# HDMI.net
KiCad netlist of a schematic drawn in Altium Designer
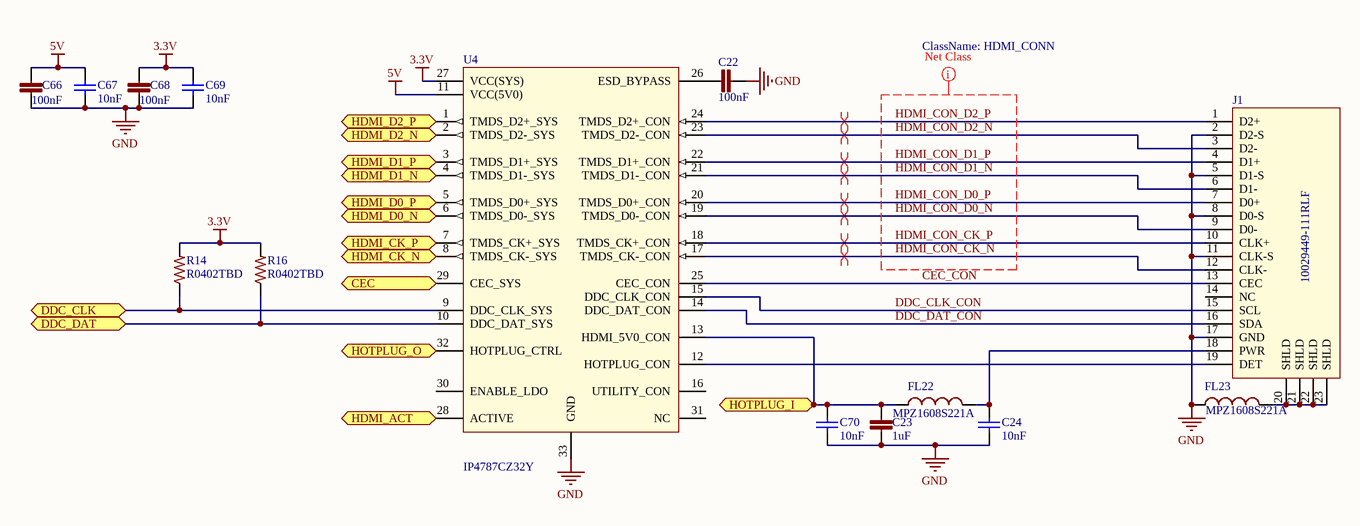
[diagram p0: HDMI.SchDoc]

(export (version "E")
  (design (tool "Eeschema 10.0.6"))
  (components
    (comp (ref "C22")
      (value "100nF")
      (footprint "C0402")
      (description "CAP CER 0402 100nF 16V 10% X7R")
      (fields
        (field (name "MANUFACTURERPARTNUMBER") "GRM155R71C104KA88D")
        (field (name "PUBLISHER") "UltiMachine")
      )
      (libsource (lib "") (part "GRM155R71C104KA88D_1"))
    )
    (comp (ref "C23")
      (value "1uF")
      (footprint "C0402")
      (description "CAP CER 0402 1uF 6.3V 10% X5R")
      (fields
        (field (name "MANUFACTURERPARTNUMBER") "GRM155R60J105KE19D")
        (field (name "PUBLISHER") "UltiMachine")
      )
      (libsource (lib "3Delight") (part "GRM155R60J105KE19D"))
    )
    (comp (ref "C24")
      (value "10nF")
      (footprint "C0402")
      (description "CAP CER 10nF 50V X7R 0402")
      (fields
        (field (name "MFR PART #") "GRM155R71H103JA88D")
        (field (name "MFR") "Murata")
        (field (name "PUBLISHER") "Ultimachine")
      )
      (libsource (lib "Tigershark3D") (part "GRM155R71H103JA88D"))
    )
    (comp (ref "C66")
      (value "100nF")
      (footprint "C0402")
      (description "CAP CER 0402 100nF 16V 10% X7R")
      (fields
        (field (name "MANUFACTURERPARTNUMBER") "GRM155R71C104KA88D")
        (field (name "PUBLISHER") "UltiMachine")
      )
      (libsource (lib "3Delight") (part "GRM155R71C104KA88D"))
    )
    (comp (ref "C67")
      (value "10nF")
      (footprint "C0402")
      (description "CAP CER 10nF 50V X7R 0402")
      (fields
        (field (name "MFR PART #") "GRM155R71H103JA88D")
        (field (name "MFR") "Murata")
        (field (name "PUBLISHER") "Ultimachine")
      )
      (libsource (lib "Tigershark3D") (part "GRM155R71H103JA88D"))
    )
    (comp (ref "C68")
      (value "100nF")
      (footprint "C0402")
      (description "CAP CER 0402 100nF 16V 10% X7R")
      (fields
        (field (name "MANUFACTURERPARTNUMBER") "GRM155R71C104KA88D")
        (field (name "PUBLISHER") "UltiMachine")
      )
      (libsource (lib "3Delight") (part "GRM155R71C104KA88D"))
    )
    (comp (ref "C69")
      (value "10nF")
      (footprint "C0402")
      (description "CAP CER 10nF 50V X7R 0402")
      (fields
        (field (name "MFR PART #") "GRM155R71H103JA88D")
        (field (name "MFR") "Murata")
        (field (name "PUBLISHER") "Ultimachine")
      )
      (libsource (lib "Tigershark3D") (part "GRM155R71H103JA88D"))
    )
    (comp (ref "C70")
      (value "10nF")
      (footprint "C0402")
      (description "CAP CER 10nF 50V X7R 0402")
      (fields
        (field (name "MFR PART #") "GRM155R71H103JA88D")
        (field (name "MFR") "Murata")
        (field (name "PUBLISHER") "Ultimachine")
      )
      (libsource (lib "Tigershark3D") (part "GRM155R71H103JA88D"))
    )
    (comp (ref "FL22")
      (value "MPZ1608S221A")
      (footprint "C0603")
      (description "Ferrite")
      (fields (field (name "PUBLISHER") "UltiMachine"))
      (libsource (lib "3Delight") (part "MPZ1608S221A"))
    )
    (comp (ref "FL23")
      (value "MPZ1608S221A")
      (footprint "C0603")
      (description "Ferrite")
      (fields (field (name "PUBLISHER") "UltiMachine"))
      (libsource (lib "3Delight") (part "MPZ1608S221A"))
    )
    (comp (ref "J1")
      (value "10029449-111RLF")
      (footprint "10029449-111RLF")
      (description "CONN HDMI RECPT 19POS SMT R/A")
      (libsource (lib "hmi") (part "10029449-111RLF"))
    )
    (comp (ref "R14")
      (value "R0402TBD")
      (footprint "R0402")
      (description "Resistor")
      (fields (field (name "PUBLISHER") "UltiMachine"))
      (libsource (lib "3Delight") (part "R0402TBD"))
    )
    (comp (ref "R16")
      (value "R0402TBD")
      (footprint "R0402")
      (description "Resistor")
      (fields (field (name "PUBLISHER") "UltiMachine"))
      (libsource (lib "3Delight") (part "R0402TBD"))
    )
    (comp (ref "U4")
      (value "IP4787CZ32Y")
      (footprint "QFN32-HVQFN32")
      (description "IC DVI/HDMI ESD PROTECT 32HVQFN")
      (libsource (lib "hmi") (part "IP4787CZ32Y"))
    )
  )
  (nets
    (net (code "1") (name "/CEC") (class "Default")
      (node (ref "U4") (pin "29") (pinfunction "CEC_SYS_29") (pintype "power_in"))
    )
    (net (code "2") (name "/CEC_CON") (class "Default")
      (node (ref "J1") (pin "13") (pinfunction "CEC_13") (pintype "power_in"))
      (node (ref "U4") (pin "25") (pinfunction "CEC_CON_25") (pintype "power_in"))
    )
    (net (code "3") (name "/DDC_CLK") (class "Default")
      (node (ref "R14") (pin "1") (pinfunction "1_1") (pintype "passive"))
      (node (ref "U4") (pin "9") (pinfunction "DDC_CLK_SYS_9") (pintype "power_in"))
    )
    (net (code "4") (name "/DDC_CLK_CON") (class "Default")
      (node (ref "J1") (pin "15") (pinfunction "SCL_15") (pintype "power_in"))
      (node (ref "U4") (pin "15") (pinfunction "DDC_CLK_CON_15") (pintype "power_in"))
    )
    (net (code "5") (name "/DDC_DAT") (class "Default")
      (node (ref "R16") (pin "1") (pinfunction "1_1") (pintype "passive"))
      (node (ref "U4") (pin "10") (pinfunction "DDC_DAT_SYS_10") (pintype "power_in"))
    )
    (net (code "6") (name "/DDC_DAT_CON") (class "Default")
      (node (ref "J1") (pin "16") (pinfunction "SDA_16") (pintype "power_in"))
      (node (ref "U4") (pin "14") (pinfunction "DDC_DAT_CON_14") (pintype "power_in"))
    )
    (net (code "7") (name "/HDMI_ACT") (class "Default")
      (node (ref "U4") (pin "28") (pinfunction "ACTIVE_28") (pintype "power_in"))
    )
    (net (code "8") (name "/HDMI_CK_N") (class "Default")
      (node (ref "U4") (pin "8") (pinfunction "TMDS_CK-_SYS_8") (pintype "output"))
    )
    (net (code "9") (name "/HDMI_CK_P") (class "Default")
      (node (ref "U4") (pin "7") (pinfunction "TMDS_CK+_SYS_7") (pintype "output"))
    )
    (net (code "10") (name "/HDMI_CON_CK_N") (class "Default")
      (node (ref "J1") (pin "12") (pinfunction "CLK-_12") (pintype "power_in"))
      (node (ref "U4") (pin "17") (pinfunction "TMDS_CK-_CON_17") (pintype "input"))
    )
    (net (code "11") (name "/HDMI_CON_CK_P") (class "Default")
      (node (ref "J1") (pin "10") (pinfunction "CLK+_10") (pintype "power_in"))
      (node (ref "U4") (pin "18") (pinfunction "TMDS_CK+_CON_18") (pintype "input"))
    )
    (net (code "12") (name "/HDMI_CON_D0_N") (class "Default")
      (node (ref "J1") (pin "9") (pinfunction "D0-_9") (pintype "power_in"))
      (node (ref "U4") (pin "19") (pinfunction "TMDS_D0-_CON_19") (pintype "input"))
    )
    (net (code "13") (name "/HDMI_CON_D0_P") (class "Default")
      (node (ref "J1") (pin "7") (pinfunction "D0+_7") (pintype "power_in"))
      (node (ref "U4") (pin "20") (pinfunction "TMDS_D0+_CON_20") (pintype "input"))
    )
    (net (code "14") (name "/HDMI_CON_D1_N") (class "Default")
      (node (ref "J1") (pin "6") (pinfunction "D1-_6") (pintype "power_in"))
      (node (ref "U4") (pin "21") (pinfunction "TMDS_D1-_CON_21") (pintype "input"))
    )
    (net (code "15") (name "/HDMI_CON_D1_P") (class "Default")
      (node (ref "J1") (pin "4") (pinfunction "D1+_4") (pintype "power_in"))
      (node (ref "U4") (pin "22") (pinfunction "TMDS_D1+_CON_22") (pintype "input"))
    )
    (net (code "16") (name "/HDMI_CON_D2_N") (class "Default")
      (node (ref "J1") (pin "3") (pinfunction "D2-_3") (pintype "power_in"))
      (node (ref "U4") (pin "23") (pinfunction "TMDS_D2-_CON_23") (pintype "input"))
    )
    (net (code "17") (name "/HDMI_CON_D2_P") (class "Default")
      (node (ref "J1") (pin "1") (pinfunction "D2+_1") (pintype "power_in"))
      (node (ref "U4") (pin "24") (pinfunction "TMDS_D2+_CON_24") (pintype "input"))
    )
    (net (code "18") (name "/HDMI_D0_N") (class "Default")
      (node (ref "U4") (pin "6") (pinfunction "TMDS_D0-_SYS_6") (pintype "output"))
    )
    (net (code "19") (name "/HDMI_D0_P") (class "Default")
      (node (ref "U4") (pin "5") (pinfunction "TMDS_D0+_SYS_5") (pintype "output"))
    )
    (net (code "20") (name "/HDMI_D1_N") (class "Default")
      (node (ref "U4") (pin "4") (pinfunction "TMDS_D1-_SYS_4") (pintype "output"))
    )
    (net (code "21") (name "/HDMI_D1_P") (class "Default")
      (node (ref "U4") (pin "3") (pinfunction "TMDS_D1+_SYS_3") (pintype "output"))
    )
    (net (code "22") (name "/HDMI_D2_N") (class "Default")
      (node (ref "U4") (pin "2") (pinfunction "TMDS_D2-_SYS_2") (pintype "output"))
    )
    (net (code "23") (name "/HDMI_D2_P") (class "Default")
      (node (ref "U4") (pin "1") (pinfunction "TMDS_D2+_SYS_1") (pintype "output"))
    )
    (net (code "24") (name "/HOTPLUG_I") (class "Default")
      (node (ref "C23") (pin "1") (pinfunction "1_1") (pintype "passive"))
      (node (ref "C70") (pin "2") (pinfunction "2_2") (pintype "passive"))
      (node (ref "FL22") (pin "1") (pinfunction "1_1") (pintype "passive"))
      (node (ref "U4") (pin "13") (pinfunction "HDMI_5V0_CON_13") (pintype "power_in"))
    )
    (net (code "25") (name "/HOTPLUG_O") (class "Default")
      (node (ref "U4") (pin "32") (pinfunction "HOTPLUG_CTRL_32") (pintype "power_in"))
    )
    (net (code "26") (name "3.3V") (class "Default")
      (node (ref "C68") (pin "1") (pinfunction "1_1") (pintype "passive"))
      (node (ref "C69") (pin "2") (pinfunction "2_2") (pintype "passive"))
      (node (ref "R14") (pin "2") (pinfunction "2_2") (pintype "passive"))
      (node (ref "R16") (pin "2") (pinfunction "2_2") (pintype "passive"))
      (node (ref "U4") (pin "27") (pinfunction "VCC(SYS)_27") (pintype "power_in"))
    )
    (net (code "27") (name "5V") (class "Default")
      (node (ref "C66") (pin "1") (pinfunction "1_1") (pintype "passive"))
      (node (ref "C67") (pin "2") (pinfunction "2_2") (pintype "passive"))
      (node (ref "U4") (pin "11") (pinfunction "VCC(5V0)_11") (pintype "power_in"))
    )
    (net (code "28") (name "GND") (class "Default")
      (node (ref "C22") (pin "2") (pinfunction "2_2") (pintype "passive"))
      (node (ref "C23") (pin "2") (pinfunction "2_2") (pintype "passive"))
      (node (ref "C24") (pin "1") (pinfunction "1_1") (pintype "passive"))
      (node (ref "C66") (pin "2") (pinfunction "2_2") (pintype "passive"))
      (node (ref "C67") (pin "1") (pinfunction "1_1") (pintype "passive"))
      (node (ref "C68") (pin "2") (pinfunction "2_2") (pintype "passive"))
      (node (ref "C69") (pin "1") (pinfunction "1_1") (pintype "passive"))
      (node (ref "C70") (pin "1") (pinfunction "1_1") (pintype "passive"))
      (node (ref "FL23") (pin "1") (pinfunction "1_1") (pintype "passive"))
      (node (ref "J1") (pin "11") (pinfunction "CLK-S_11") (pintype "power_in"))
      (node (ref "J1") (pin "17") (pinfunction "GND_17") (pintype "power_in"))
      (node (ref "J1") (pin "2") (pinfunction "D2-S_2") (pintype "power_in"))
      (node (ref "J1") (pin "5") (pinfunction "D1-S_5") (pintype "power_in"))
      (node (ref "J1") (pin "8") (pinfunction "D0-S_8") (pintype "power_in"))
      (node (ref "U4") (pin "33") (pinfunction "GND_33") (pintype "power_in"))
    )
    (net (code "29") (name "Net-(FL23-Pad2)") (class "Default")
      (node (ref "FL23") (pin "2") (pinfunction "2_2") (pintype "passive"))
      (node (ref "J1") (pin "20") (pinfunction "SHLD_20") (pintype "power_in"))
      (node (ref "J1") (pin "21") (pinfunction "SHLD_21") (pintype "power_in"))
      (node (ref "J1") (pin "22") (pinfunction "SHLD_22") (pintype "power_in"))
      (node (ref "J1") (pin "23") (pinfunction "SHLD_23") (pintype "power_in"))
    )
    (net (code "30") (name "Net-(J1-DET)") (class "Default")
      (node (ref "J1") (pin "19") (pinfunction "DET_19") (pintype "power_in"))
      (node (ref "U4") (pin "12") (pinfunction "HOTPLUG_CON_12") (pintype "power_in"))
    )
    (net (code "31") (name "Net-(J1-PWR)") (class "Default")
      (node (ref "C24") (pin "2") (pinfunction "2_2") (pintype "passive"))
      (node (ref "FL22") (pin "2") (pinfunction "2_2") (pintype "passive"))
      (node (ref "J1") (pin "18") (pinfunction "PWR_18") (pintype "power_in"))
    )
    (net (code "32") (name "Net-(U4-ESD_BYPASS)") (class "Default")
      (node (ref "C22") (pin "1") (pinfunction "1_1") (pintype "passive"))
      (node (ref "U4") (pin "26") (pinfunction "ESD_BYPASS_26") (pintype "power_in"))
    )
    (net (code "33") (name "unconnected-(J1-NC-Pad14)") (class "Default")
      (node (ref "J1") (pin "14") (pinfunction "NC_14") (pintype "power_in"))
    )
    (net (code "34") (name "unconnected-(U4-ENABLE_LDO-Pad30)") (class "Default")
      (node (ref "U4") (pin "30") (pinfunction "ENABLE_LDO_30") (pintype "power_in"))
    )
    (net (code "35") (name "unconnected-(U4-NC-Pad31)") (class "Default")
      (node (ref "U4") (pin "31") (pinfunction "NC_31") (pintype "power_in"))
    )
    (net (code "36") (name "unconnected-(U4-UTILITY_CON-Pad16)") (class "Default")
      (node (ref "U4") (pin "16") (pinfunction "UTILITY_CON_16") (pintype "power_in"))
    )
  )
)
